# Sheet1.net
KiCad netlist of a schematic drawn in Altium Designer
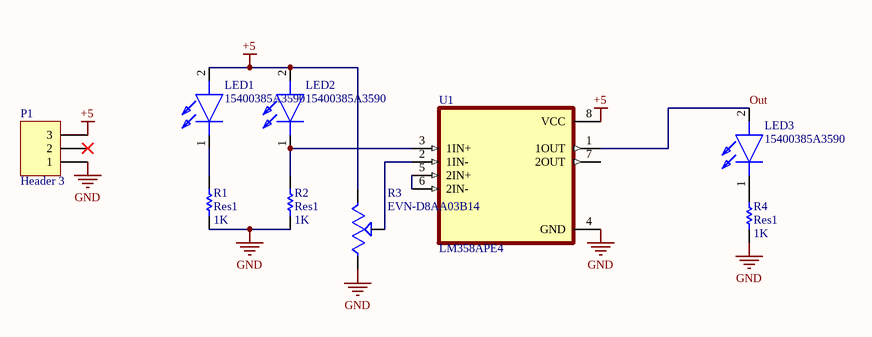
[diagram p0: Sheet1.SchDoc]

(export (version "E")
  (design (tool "Eeschema 10.0.6"))
  (components
    (comp (ref "LED1")
      (value "15400385A3590")
      (footprint "SamacSys:15400385A3590")
      (description "LED")
      (fields (field (name "MOUSER PART NUMBER") "710-15400385A3590"))
      (libsource (lib "SamacSys") (part "15400385A3590"))
    )
    (comp (ref "LED2")
      (value "15400385A3590")
      (footprint "SamacSys:15400385A3590")
      (description "LED")
      (fields (field (name "MOUSER PART NUMBER") "710-15400385A3590"))
      (libsource (lib "SamacSys") (part "15400385A3590"))
    )
    (comp (ref "LED3")
      (value "15400385A3590")
      (footprint "SamacSys:15400385A3590")
      (description "LED")
      (fields (field (name "MOUSER PART NUMBER") "710-15400385A3590"))
      (libsource (lib "SamacSys") (part "15400385A3590"))
    )
    (comp (ref "P1")
      (value "Header 3")
      (footprint "HDR1X3")
      (description "Header, 3-Pin")
      (fields (field (name "PUBLISHER") "Altium Limited"))
      (libsource (lib "Miscellaneous Connectors") (part "Header 3"))
    )
    (comp (ref "R1")
      (value "Res1")
      (footprint "AXIAL-0.3")
      (description "Resistor")
      (fields (field (name "ALTIUM_VALUE") "1K") (field (name "PUBLISHER") "Altium Limited"))
      (libsource (lib "Miscellaneous Devices") (part "Res1"))
    )
    (comp (ref "R2")
      (value "Res1")
      (footprint "AXIAL-0.3")
      (description "Resistor")
      (fields (field (name "ALTIUM_VALUE") "1K") (field (name "PUBLISHER") "Altium Limited"))
      (libsource (lib "Miscellaneous Devices") (part "Res1"))
    )
    (comp (ref "R3")
      (value "EVN-D8AA03B14")
      (footprint "TRIM_EVN-D8AA03B14")
      (description "10 kOhms 0.1W, 1/10W PC Pins Through Hole Trimmer Potentiometer Carbon 1.0 Turn Top Adjustment")
      (fields (field (name "MF") "Panasonic Electronic"))
      (libsource (lib "EVN-D8AA03B14") (part "EVN-D8AA03B14"))
    )
    (comp (ref "R4")
      (value "Res1")
      (footprint "AXIAL-0.3")
      (description "Resistor")
      (fields (field (name "ALTIUM_VALUE") "1K") (field (name "PUBLISHER") "Altium Limited"))
      (libsource (lib "Miscellaneous Devices") (part "Res1"))
    )
    (comp (ref "U1")
      (value "LM358APE4")
      (footprint "DIP794W45P254L959H508Q8")
      (description "Dual, 30-V, 700-kHz operational amplifier")
      (fields (field (name "MF") "Texas Instruments"))
      (libsource (lib "LM358APE4") (part "LM358APE4"))
    )
  )
  (nets
    (net (code "1") (name "+5") (class "Default")
      (node (ref "LED1") (pin "2") (pinfunction "A_2") (pintype "passive"))
      (node (ref "LED2") (pin "2") (pinfunction "A_2") (pintype "passive"))
      (node (ref "P1") (pin "3") (pinfunction "3_3") (pintype "passive"))
      (node (ref "R3") (pin "3") (pinfunction "3_3") (pintype "passive"))
      (node (ref "U1") (pin "8") (pinfunction "VCC_8") (pintype "power_in"))
    )
    (net (code "2") (name "/Out") (class "Default")
      (node (ref "LED3") (pin "2") (pinfunction "A_2") (pintype "passive"))
      (node (ref "U1") (pin "1") (pinfunction "1OUT_1") (pintype "output"))
    )
    (net (code "3") (name "GND") (class "Default")
      (node (ref "P1") (pin "1") (pinfunction "1_1") (pintype "passive"))
      (node (ref "R1") (pin "1") (pinfunction "1_1") (pintype "passive"))
      (node (ref "R2") (pin "1") (pinfunction "1_1") (pintype "passive"))
      (node (ref "R3") (pin "1") (pinfunction "1_1") (pintype "passive"))
      (node (ref "R4") (pin "1") (pinfunction "1_1") (pintype "passive"))
      (node (ref "U1") (pin "4") (pinfunction "GND_4") (pintype "power_in"))
    )
    (net (code "4") (name "Net-(LED1-K)") (class "Default")
      (node (ref "LED1") (pin "1") (pinfunction "K_1") (pintype "passive"))
      (node (ref "R1") (pin "2") (pinfunction "2_2") (pintype "passive"))
    )
    (net (code "5") (name "Net-(LED2-K)") (class "Default")
      (node (ref "LED2") (pin "1") (pinfunction "K_1") (pintype "passive"))
      (node (ref "R2") (pin "2") (pinfunction "2_2") (pintype "passive"))
      (node (ref "U1") (pin "3") (pinfunction "1IN+_3") (pintype "input"))
    )
    (net (code "6") (name "Net-(LED3-K)") (class "Default")
      (node (ref "LED3") (pin "1") (pinfunction "K_1") (pintype "passive"))
      (node (ref "R4") (pin "2") (pinfunction "2_2") (pintype "passive"))
    )
    (net (code "7") (name "Net-(U1-1IN-)") (class "Default")
      (node (ref "R3") (pin "2") (pinfunction "2_2") (pintype "passive"))
      (node (ref "U1") (pin "2") (pinfunction "1IN-_2") (pintype "input"))
    )
    (net (code "8") (name "Net-(U1-2IN+)") (class "Default")
      (node (ref "U1") (pin "5") (pinfunction "2IN+_5") (pintype "input"))
      (node (ref "U1") (pin "6") (pinfunction "2IN-_6") (pintype "input"))
    )
    (net (code "9") (name "unconnected-(P1-Pad2)") (class "Default")
      (node (ref "P1") (pin "2") (pinfunction "2_2") (pintype "passive+no_connect"))
    )
    (net (code "10") (name "unconnected-(U1-2OUT-Pad7)") (class "Default")
      (node (ref "U1") (pin "7") (pinfunction "2OUT_7") (pintype "output"))
    )
  )
)
